# motordriver-v5_0_connectors.net
KiCad netlist of a schematic drawn in Altium Designer
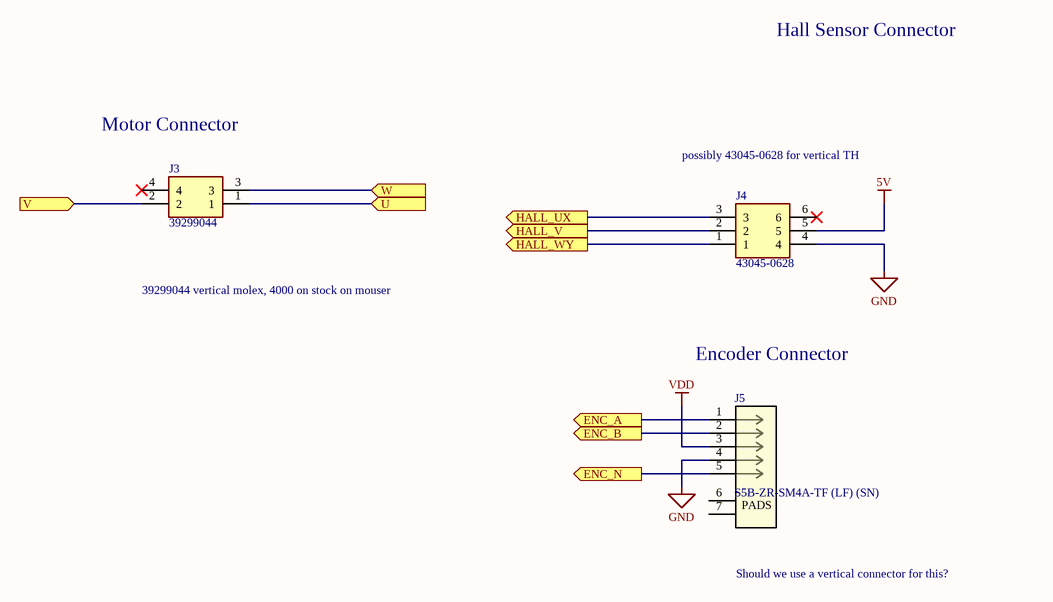
[diagram p0: motordriver-v5.0_connectors.SchDoc]

(export (version "E")
  (design (tool "Eeschema 10.0.6"))
  (components
    (comp (ref "J3")
      (value "39299044")
      (footprint "39299044")
      (description "Molex 39299044 4POS Minifit\r\ndual row, vertical")
      (fields (field (name "PART NUMBER") "CN HDR 4POS Molex 39299044 VERT"))
      (libsource (lib "Connector_Library") (part "CN HDR 4POS Molex 39299044 VERT"))
    )
    (comp (ref "J4")
      (value "43045-0628")
      (footprint "430450628")
      (description "Molex 43045-0628 6POS Microfit\r\ndual row, Vertical")
      (fields
        (field (name "PART NUMBER") "CN HDR 6POS Molex 43045-0628")
        (field (name "MANUFACTURER PART NUMBER") "430450628")
      )
      (libsource (lib "Connector_Library") (part "CN HDR 6POS Molex 43045-0628"))
    )
    (comp (ref "J5")
      (value "S5B-ZR-SM4A-TF (LF) (SN)")
      (footprint "JST_S5B-ZR-SM4A-TF")
      (description "Connector Header Surface Mount, Right Angle 5 position 0.059\" (1.50mm)")
      (fields
        (field (name "PART NUMBER") "CN 5POS JST ZR RA")
        (field (name "MANUFACTURER PART NUMBER") "S5B-ZR-SM4A-TF")
      )
      (libsource (lib "Connector_Library") (part "CN 5POS JST ZR RA"))
    )
  )
  (nets
    (net (code "1") (name "/ENC_A") (class "Default")
      (node (ref "J5") (pin "1") (pinfunction "1_1") (pintype "passive"))
    )
    (net (code "2") (name "/ENC_B") (class "Default")
      (node (ref "J5") (pin "2") (pinfunction "2_2") (pintype "passive"))
    )
    (net (code "3") (name "/ENC_N") (class "Default")
      (node (ref "J5") (pin "5") (pinfunction "5_5") (pintype "passive"))
    )
    (net (code "4") (name "/HALL_UX") (class "Default")
      (node (ref "J4") (pin "3") (pinfunction "3_3") (pintype "passive"))
    )
    (net (code "5") (name "/HALL_V") (class "Default")
      (node (ref "J4") (pin "2") (pinfunction "2_2") (pintype "passive"))
    )
    (net (code "6") (name "/HALL_WY") (class "Default")
      (node (ref "J4") (pin "1") (pinfunction "1_1") (pintype "passive"))
    )
    (net (code "7") (name "/U") (class "Default")
      (node (ref "J3") (pin "1") (pinfunction "1_1") (pintype "passive"))
    )
    (net (code "8") (name "/V") (class "Default")
      (node (ref "J3") (pin "2") (pinfunction "2_2") (pintype "passive"))
    )
    (net (code "9") (name "/W") (class "Default")
      (node (ref "J3") (pin "3") (pinfunction "3_3") (pintype "passive"))
    )
    (net (code "10") (name "5V") (class "Default")
      (node (ref "J4") (pin "5") (pinfunction "5_5") (pintype "passive"))
    )
    (net (code "11") (name "GND") (class "Default")
      (node (ref "J4") (pin "4") (pinfunction "4_4") (pintype "passive"))
      (node (ref "J5") (pin "4") (pinfunction "4_4") (pintype "passive"))
    )
    (net (code "12") (name "VDD") (class "Default")
      (node (ref "J5") (pin "3") (pinfunction "3_3") (pintype "passive"))
    )
    (net (code "13") (name "unconnected-(J3-Pad4)") (class "Default")
      (node (ref "J3") (pin "4") (pinfunction "4_4") (pintype "passive+no_connect"))
    )
    (net (code "14") (name "unconnected-(J4-Pad6)") (class "Default")
      (node (ref "J4") (pin "6") (pinfunction "6_6") (pintype "passive+no_connect"))
    )
    (net (code "15") (name "unconnected-(J5-Pad6)") (class "Default")
      (node (ref "J5") (pin "6") (pinfunction "6_6") (pintype "passive"))
    )
    (net (code "16") (name "unconnected-(J5-Pad7)") (class "Default")
      (node (ref "J5") (pin "7") (pinfunction "7_7") (pintype "passive"))
    )
  )
)
